# EEPROM_Temp.net
KiCad netlist of a schematic drawn in Altium Designer
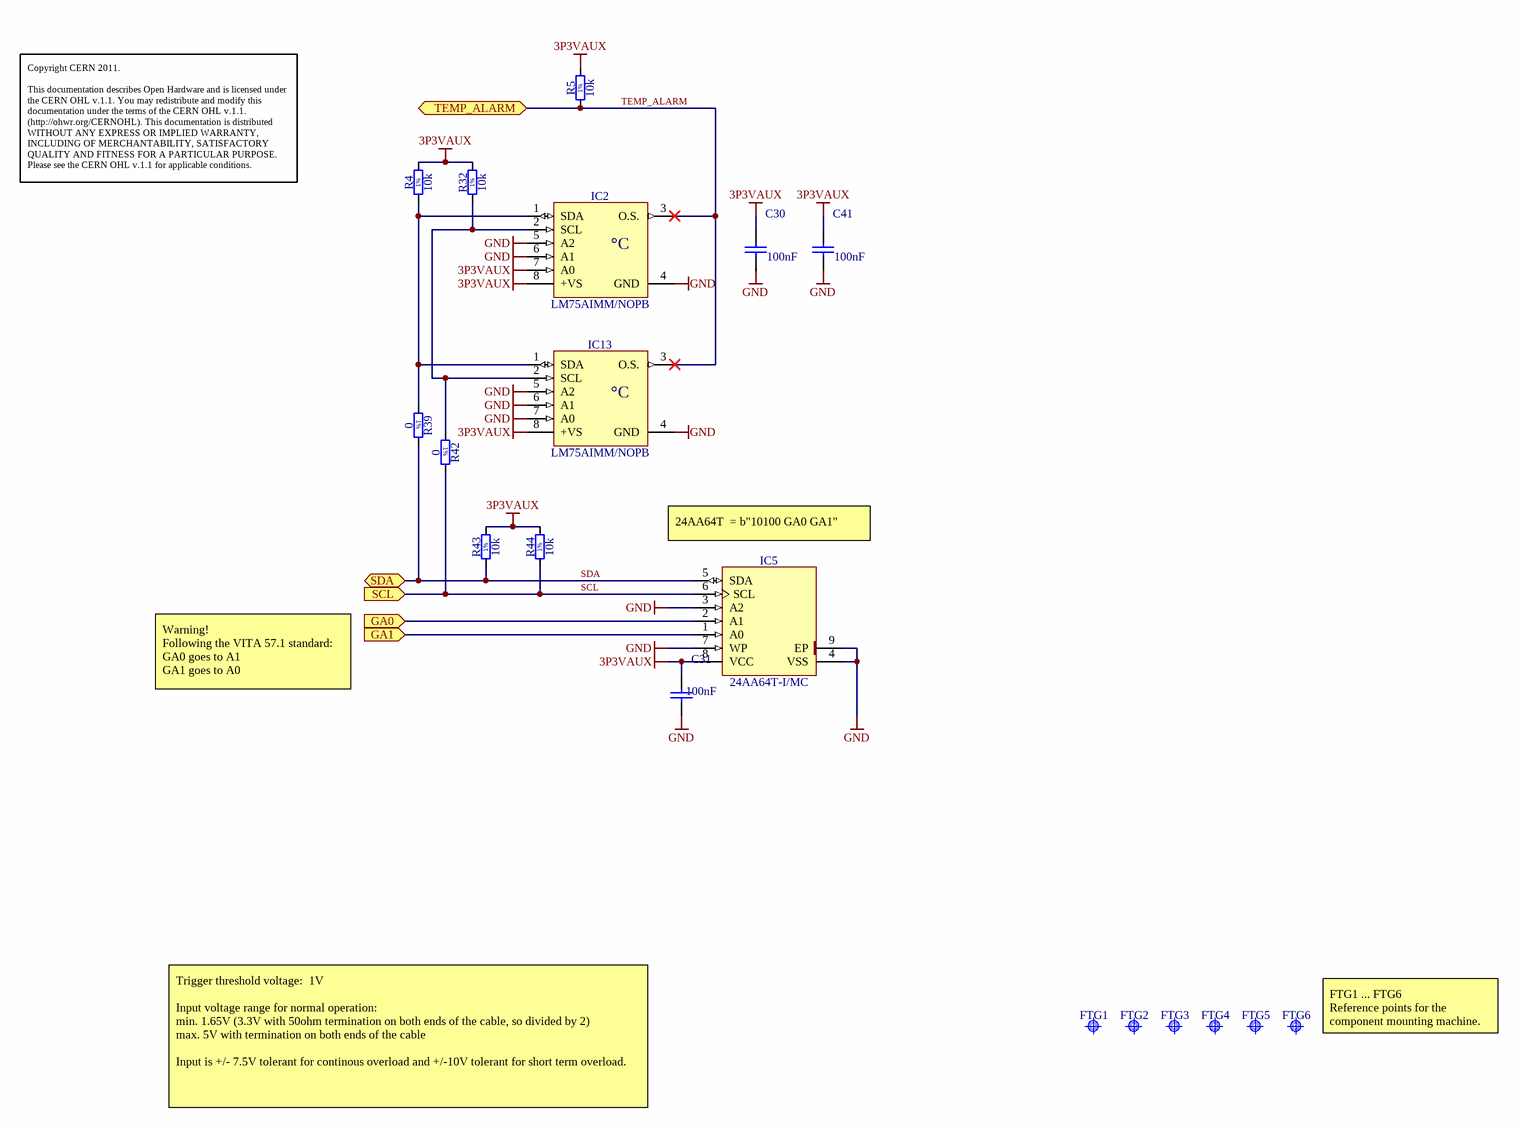
[diagram p0: EEPROM_Temp.SchDoc]

(export (version "E")
  (design (tool "Eeschema 10.0.6"))
  (components
    (comp (ref "C30")
      (value "100nF")
      (footprint "CAPC0603X33N")
      (description "Non-polarised capacitor")
      (fields
        (field (name "PART NUMBER") "CC0201_100NF_6.3V_10%_X5R")
        (field (name "VOLTAGE") "6.3V")
        (field (name "AUTHOR") "CERN DEM JLC")
      )
      (libsource (lib "Capacitors") (part "Capacitor - non polarized"))
    )
    (comp (ref "C31")
      (value "100nF")
      (footprint "CAPC0603X33N")
      (description "Non-polarised capacitor")
      (fields
        (field (name "PART NUMBER") "CC0201_100NF_6.3V_10%_X5R")
        (field (name "VOLTAGE") "6.3V")
        (field (name "AUTHOR") "CERN DEM JLC")
      )
      (libsource (lib "Capacitors") (part "Capacitor - non polarized"))
    )
    (comp (ref "C41")
      (value "100nF")
      (footprint "CAPC0603X33N")
      (description "Non-polarised capacitor")
      (fields
        (field (name "PART NUMBER") "CC0201_100NF_6.3V_10%_X5R")
        (field (name "VOLTAGE") "6.3V")
        (field (name "AUTHOR") "CERN DEM JLC")
      )
      (libsource (lib "Capacitors") (part "Capacitor - non polarized"))
    )
    (comp (ref "FTG1")
      (value "Use only in PCB")
      (footprint "FIDUCIAL_TOP_S100-200")
      (description "Fiducial Target")
      (fields (field (name "PART NUMBER") "FIDUCIAL_TARGET_S100-200") (field (name "AUTHOR") "CERN DEM JLC"))
      (libsource (lib "Eletro-mechanical") (part "Fiducial Target"))
    )
    (comp (ref "FTG2")
      (value "Use only in PCB")
      (footprint "FIDUCIAL_TOP_S100-200")
      (description "Fiducial Target")
      (fields (field (name "PART NUMBER") "FIDUCIAL_TARGET_S100-200") (field (name "AUTHOR") "CERN DEM JLC"))
      (libsource (lib "Eletro-mechanical") (part "Fiducial Target"))
    )
    (comp (ref "FTG3")
      (value "Use only in PCB")
      (footprint "FIDUCIAL_TOP_S100-200")
      (description "Fiducial Target")
      (fields (field (name "PART NUMBER") "FIDUCIAL_TARGET_S100-200") (field (name "AUTHOR") "CERN DEM JLC"))
      (libsource (lib "Eletro-mechanical") (part "Fiducial Target"))
    )
    (comp (ref "FTG4")
      (value "Use only in PCB")
      (footprint "FIDUCIAL_TOP_S100-200")
      (description "Fiducial Target")
      (fields (field (name "PART NUMBER") "FIDUCIAL_TARGET_S100-200") (field (name "AUTHOR") "CERN DEM JLC"))
      (libsource (lib "Eletro-mechanical") (part "Fiducial Target"))
    )
    (comp (ref "FTG5")
      (value "Use only in PCB")
      (footprint "FIDUCIAL_TOP_S100-200")
      (description "Fiducial Target")
      (fields (field (name "PART NUMBER") "FIDUCIAL_TARGET_S100-200") (field (name "AUTHOR") "CERN DEM JLC"))
      (libsource (lib "Eletro-mechanical") (part "Fiducial Target"))
    )
    (comp (ref "FTG6")
      (value "Use only in PCB")
      (footprint "FIDUCIAL_TOP_S100-200")
      (description "Fiducial Target")
      (fields (field (name "PART NUMBER") "FIDUCIAL_TARGET_S100-200") (field (name "AUTHOR") "CERN DEM JLC"))
      (libsource (lib "Eletro-mechanical") (part "Fiducial Target"))
    )
    (comp (ref "IC2")
      (value "LM75AIMM/NOPB")
      (footprint "SOP65P490X109-8N")
      (description "Digital Temperature Sensor and Thermal Watchdog with Two-Wire Interface")
      (fields (field (name "MANUFACTURER") "TEXAS INSTRUMENTS") (field (name "AUTHOR") "CERN DEM JLC"))
      (libsource (lib "ICs And Semiconductors") (part "LM75"))
    )
    (comp (ref "IC5")
      (value "24AA64T-I/MC")
      (footprint "SON50P300X200X100-9N-S175X155")
      (description "1.7-5.5V 64K I2C Serial EEPROM")
      (fields (field (name "MANUFACTURER") "MICROCHIP TECHNOLOGY") (field (name "AUTHOR") "CERN DEM JLC"))
      (libsource (lib "ICs And Semiconductors") (part "24AA64T-I/MC"))
    )
    (comp (ref "IC13")
      (value "LM75AIMM/NOPB")
      (footprint "SOP65P490X109-8N")
      (description "Digital Temperature Sensor and Thermal Watchdog with Two-Wire Interface")
      (fields (field (name "MANUFACTURER") "TEXAS INSTRUMENTS") (field (name "AUTHOR") "CERN DEM JLC"))
      (libsource (lib "ICs And Semiconductors") (part "LM75"))
    )
    (comp (ref "R4")
      (value "10k")
      (footprint "RESC1005X40N")
      (description "Resistor - 1%")
      (fields
        (field (name "PART NUMBER") "R0402_10K_1%_0.0625W_100PPM")
        (field (name "POWER") "0.0625W")
        (field (name "AUTHOR") "CERN DEM JLC")
      )
      (libsource (lib "Resistors") (part "Resistor - 1%"))
    )
    (comp (ref "R5")
      (value "10k")
      (footprint "RESC1005X40N")
      (description "Resistor - 1%")
      (fields
        (field (name "PART NUMBER") "R0402_10K_1%_0.0625W_100PPM")
        (field (name "POWER") "0.0625W")
        (field (name "AUTHOR") "CERN DEM JLC")
      )
      (libsource (lib "Resistors") (part "Resistor - 1%"))
    )
    (comp (ref "R32")
      (value "10k")
      (footprint "RESC1005X40N")
      (description "Resistor - 1%")
      (fields
        (field (name "PART NUMBER") "R0402_10K_1%_0.0625W_100PPM")
        (field (name "POWER") "0.0625W")
        (field (name "AUTHOR") "CERN DEM JLC")
      )
      (libsource (lib "Resistors") (part "Resistor - 1%"))
    )
    (comp (ref "R39")
      (value "0")
      (footprint "RESC1005X40N")
      (description "Resistor - 1%")
      (fields
        (field (name "PART NUMBER") "R0402_0R_JUMPER")
        (field (name "MANUFACTURER") "GENERIC")
        (field (name "AUTHOR") "CERN DEM JLC")
      )
      (libsource (lib "Resistors") (part "Resistor - 1%"))
    )
    (comp (ref "R42")
      (value "0")
      (footprint "RESC1005X40N")
      (description "Resistor - 1%")
      (fields
        (field (name "PART NUMBER") "R0402_0R_JUMPER")
        (field (name "MANUFACTURER") "GENERIC")
        (field (name "AUTHOR") "CERN DEM JLC")
      )
      (libsource (lib "Resistors") (part "Resistor - 1%"))
    )
    (comp (ref "R43")
      (value "10k")
      (footprint "RESC1005X40N")
      (description "Resistor - 1%")
      (fields
        (field (name "PART NUMBER") "R0402_10K_1%_0.0625W_100PPM")
        (field (name "POWER") "0.0625W")
        (field (name "AUTHOR") "CERN DEM JLC")
      )
      (libsource (lib "Resistors") (part "Resistor - 1%"))
    )
    (comp (ref "R44")
      (value "10k")
      (footprint "RESC1005X40N")
      (description "Resistor - 1%")
      (fields
        (field (name "PART NUMBER") "R0402_10K_1%_0.0625W_100PPM")
        (field (name "POWER") "0.0625W")
        (field (name "AUTHOR") "CERN DEM JLC")
      )
      (libsource (lib "Resistors") (part "Resistor - 1%"))
    )
  )
  (nets
    (net (code "1") (name "/GA0") (class "Default")
      (node (ref "IC5") (pin "2") (pinfunction "A1_2") (pintype "input"))
    )
    (net (code "2") (name "/GA1") (class "Default")
      (node (ref "IC5") (pin "1") (pinfunction "A0_1") (pintype "input"))
    )
    (net (code "3") (name "/SCL") (class "Default")
      (node (ref "IC5") (pin "6") (pinfunction "SCL_6") (pintype "input"))
      (node (ref "R42") (pin "2") (pinfunction "2_2") (pintype "passive"))
      (node (ref "R44") (pin "1") (pinfunction "1_1") (pintype "passive"))
    )
    (net (code "4") (name "/SDA") (class "Default")
      (node (ref "IC5") (pin "5") (pinfunction "SDA_5") (pintype "bidirectional"))
      (node (ref "R39") (pin "2") (pinfunction "2_2") (pintype "passive"))
      (node (ref "R43") (pin "1") (pinfunction "1_1") (pintype "passive"))
    )
    (net (code "5") (name "/TEMP_ALARM") (class "Default")
      (node (ref "IC13") (pin "3") (pinfunction "O.S._3") (pintype "output"))
      (node (ref "IC2") (pin "3") (pinfunction "O.S._3") (pintype "output"))
      (node (ref "R5") (pin "1") (pinfunction "1_1") (pintype "passive"))
    )
    (net (code "6") (name "3P3VAUX") (class "Default")
      (node (ref "C30") (pin "1") (pinfunction "1_1") (pintype "passive"))
      (node (ref "C31") (pin "1") (pinfunction "1_1") (pintype "passive"))
      (node (ref "C41") (pin "1") (pinfunction "1_1") (pintype "passive"))
      (node (ref "IC13") (pin "8") (pinfunction "+VS_8") (pintype "power_in"))
      (node (ref "IC2") (pin "7") (pinfunction "A0_7") (pintype "input"))
      (node (ref "IC2") (pin "8") (pinfunction "+VS_8") (pintype "power_in"))
      (node (ref "IC5") (pin "8") (pinfunction "VCC_8") (pintype "power_in"))
      (node (ref "R32") (pin "2") (pinfunction "2_2") (pintype "passive"))
      (node (ref "R4") (pin "2") (pinfunction "2_2") (pintype "passive"))
      (node (ref "R43") (pin "2") (pinfunction "2_2") (pintype "passive"))
      (node (ref "R44") (pin "2") (pinfunction "2_2") (pintype "passive"))
      (node (ref "R5") (pin "2") (pinfunction "2_2") (pintype "passive"))
    )
    (net (code "7") (name "GND") (class "Default")
      (node (ref "C30") (pin "2") (pinfunction "2_2") (pintype "passive"))
      (node (ref "C31") (pin "2") (pinfunction "2_2") (pintype "passive"))
      (node (ref "C41") (pin "2") (pinfunction "2_2") (pintype "passive"))
      (node (ref "IC13") (pin "4") (pinfunction "GND_4") (pintype "power_in"))
      (node (ref "IC13") (pin "5") (pinfunction "A2_5") (pintype "input"))
      (node (ref "IC13") (pin "6") (pinfunction "A1_6") (pintype "input"))
      (node (ref "IC13") (pin "7") (pinfunction "A0_7") (pintype "input"))
      (node (ref "IC2") (pin "4") (pinfunction "GND_4") (pintype "power_in"))
      (node (ref "IC2") (pin "5") (pinfunction "A2_5") (pintype "input"))
      (node (ref "IC2") (pin "6") (pinfunction "A1_6") (pintype "input"))
      (node (ref "IC5") (pin "3") (pinfunction "A2_3") (pintype "input"))
      (node (ref "IC5") (pin "4") (pinfunction "VSS_4") (pintype "power_in"))
      (node (ref "IC5") (pin "7") (pinfunction "WP_7") (pintype "input"))
      (node (ref "IC5") (pin "9") (pinfunction "EP_9") (pintype "power_in"))
    )
    (net (code "8") (name "Net-(IC13-SCL)") (class "Default")
      (node (ref "IC13") (pin "2") (pinfunction "SCL_2") (pintype "input"))
      (node (ref "IC2") (pin "2") (pinfunction "SCL_2") (pintype "input"))
      (node (ref "R32") (pin "1") (pinfunction "1_1") (pintype "passive"))
      (node (ref "R42") (pin "1") (pinfunction "1_1") (pintype "passive"))
    )
    (net (code "9") (name "Net-(IC13-SDA)") (class "Default")
      (node (ref "IC13") (pin "1") (pinfunction "SDA_1") (pintype "bidirectional"))
      (node (ref "IC2") (pin "1") (pinfunction "SDA_1") (pintype "bidirectional"))
      (node (ref "R39") (pin "1") (pinfunction "1_1") (pintype "passive"))
      (node (ref "R4") (pin "1") (pinfunction "1_1") (pintype "passive"))
    )
  )
)
